# SAM4N_Xplained_Pro_Target_MCU.net
KiCad netlist of a schematic drawn in Altium Designer
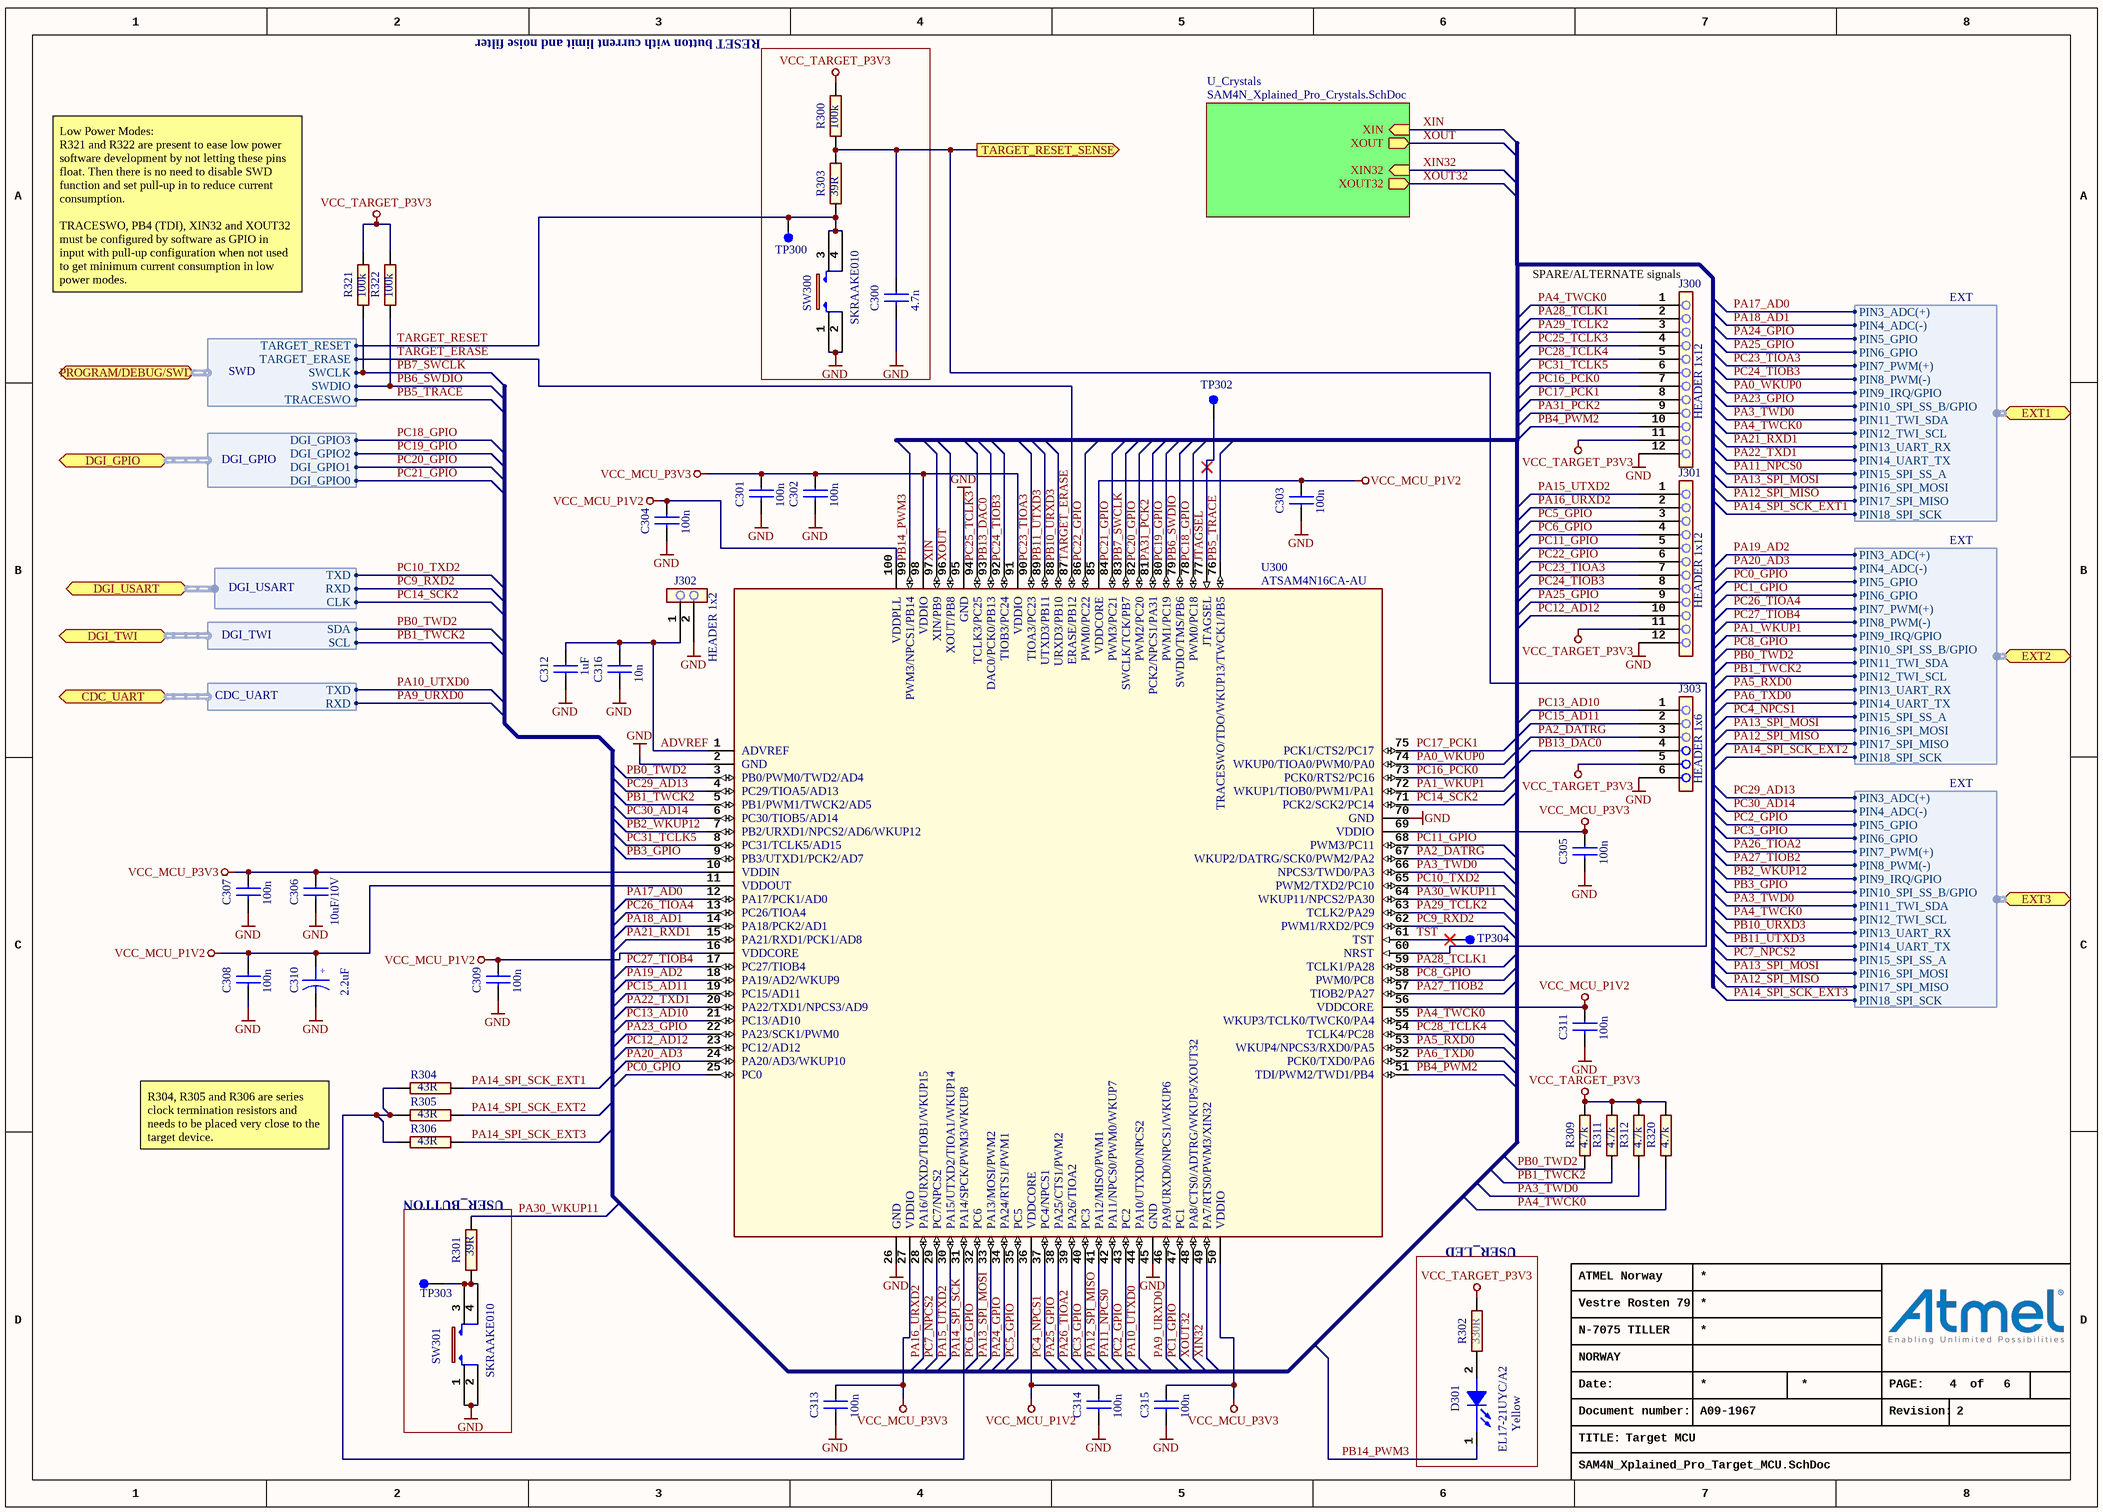
[diagram p0: SAM4N_Xplained_Pro_Target_MCU.SchDoc]

(export (version "E")
  (design (tool "Eeschema 10.0.6"))
  (components
    (comp (ref "C300")
      (value "4.7n")
      (footprint "AP1-00001")
      (description "Ceramic capacitor, SMD 0402, X7R, 25V, +/-10% (de35287)")
      (fields (field (name "TOLERANCE") "25V, +/-10%") (field (name "Comment") "CAP-NONPOL"))
      (libsource (lib "AltiumDbLib") (part "CAP-NONPOL"))
    )
    (comp (ref "C301")
      (value "100n")
      (footprint "AP1-00001")
      (description "Ceramic capacitor, SMD 0402, X7R, 16V, +/-10%")
      (fields (field (name "TOLERANCE") "16V, +/-10%") (field (name "MANUFACTURER") "Kemet"))
      (libsource (lib "AltiumDbLib") (part "CAP-NONPOL"))
    )
    (comp (ref "C302")
      (value "100n")
      (footprint "AP1-00001")
      (description "Ceramic capacitor, SMD 0402, X7R, 16V, +/-10%")
      (fields (field (name "TOLERANCE") "16V, +/-10%") (field (name "MANUFACTURER") "Kemet"))
      (libsource (lib "AltiumDbLib") (part "CAP-NONPOL"))
    )
    (comp (ref "C303")
      (value "100n")
      (footprint "AP1-00001")
      (description "Ceramic capacitor, SMD 0402, X7R, 16V, +/-10%")
      (fields (field (name "TOLERANCE") "16V, +/-10%") (field (name "MANUFACTURER") "Kemet"))
      (libsource (lib "AltiumDbLib") (part "CAP-NONPOL"))
    )
    (comp (ref "C304")
      (value "100n")
      (footprint "AP1-00001")
      (description "Ceramic capacitor, SMD 0402, X7R, 16V, +/-10%")
      (fields (field (name "TOLERANCE") "16V, +/-10%") (field (name "MANUFACTURER") "Kemet"))
      (libsource (lib "AltiumDbLib") (part "CAP-NONPOL"))
    )
    (comp (ref "C305")
      (value "100n")
      (footprint "AP1-00001")
      (description "Ceramic capacitor, SMD 0402, X7R, 16V, +/-10%")
      (fields (field (name "TOLERANCE") "16V, +/-10%") (field (name "MANUFACTURER") "Kemet"))
      (libsource (lib "AltiumDbLib") (part "CAP-NONPOL"))
    )
    (comp (ref "C306")
      (value "10uF/10V")
      (footprint "AP1-00039")
      (description "Ceramic capacitor, SMD 0603, X5R, 10V, 10UF ± 20%")
      (fields (field (name "TOLERANCE") "± 20%") (field (name "MANUFACTURER") "AVX"))
      (libsource (lib "AltiumDbLib") (part "CAP-NONPOL"))
    )
    (comp (ref "C307")
      (value "100n")
      (footprint "AP1-00001")
      (description "Ceramic capacitor, SMD 0402, X7R, 16V, +/-10%")
      (fields (field (name "TOLERANCE") "16V, +/-10%") (field (name "MANUFACTURER") "Kemet"))
      (libsource (lib "AltiumDbLib") (part "CAP-NONPOL"))
    )
    (comp (ref "C308")
      (value "100n")
      (footprint "AP1-00001")
      (description "Ceramic capacitor, SMD 0402, X7R, 16V, +/-10%")
      (fields (field (name "TOLERANCE") "16V, +/-10%") (field (name "MANUFACTURER") "Kemet"))
      (libsource (lib "AltiumDbLib") (part "CAP-NONPOL"))
    )
    (comp (ref "C309")
      (value "100n")
      (footprint "AP1-00001")
      (description "Ceramic capacitor, SMD 0402, X7R, 16V, +/-10%")
      (fields (field (name "TOLERANCE") "16V, +/-10%") (field (name "MANUFACTURER") "Kemet"))
      (libsource (lib "AltiumDbLib") (part "CAP-NONPOL"))
    )
    (comp (ref "C310")
      (value "2.2uF")
      (footprint "AP1-00036")
      (description "Capacitor Tantalum 10V 2.2uF 10% ESR = 6 ohm")
      (fields (field (name "TOLERANCE") "±10%") (field (name "MANUFACTURER") "Kemet"))
      (libsource (lib "AltiumDbLib") (part "CAP-POL"))
    )
    (comp (ref "C311")
      (value "100n")
      (footprint "AP1-00001")
      (description "Ceramic capacitor, SMD 0402, X7R, 16V, +/-10%")
      (fields (field (name "TOLERANCE") "16V, +/-10%") (field (name "MANUFACTURER") "Kemet"))
      (libsource (lib "AltiumDbLib") (part "CAP-NONPOL"))
    )
    (comp (ref "C312")
      (value "1uF")
      (footprint "AP1-00038")
      (description "Ceramic capacitor, SMD 0402, X5R, 10V, ±10 %")
      (fields (field (name "MANUFACTURER") "AVX") (field (name "MPN") "0402ZD105KAT2A"))
      (libsource (lib "AltiumDbLib") (part "CAP-NONPOL"))
    )
    (comp (ref "C313")
      (value "100n")
      (footprint "AP1-00001")
      (description "Ceramic capacitor, SMD 0402, X7R, 16V, +/-10%")
      (fields (field (name "TOLERANCE") "16V, +/-10%") (field (name "MANUFACTURER") "Kemet"))
      (libsource (lib "AltiumDbLib") (part "CAP-NONPOL"))
    )
    (comp (ref "C314")
      (value "100n")
      (footprint "AP1-00001")
      (description "Ceramic capacitor, SMD 0402, X7R, 16V, +/-10%")
      (fields (field (name "TOLERANCE") "16V, +/-10%") (field (name "MANUFACTURER") "Kemet"))
      (libsource (lib "AltiumDbLib") (part "CAP-NONPOL"))
    )
    (comp (ref "C315")
      (value "100n")
      (footprint "AP1-00001")
      (description "Ceramic capacitor, SMD 0402, X7R, 16V, +/-10%")
      (fields (field (name "TOLERANCE") "16V, +/-10%") (field (name "MANUFACTURER") "Kemet"))
      (libsource (lib "AltiumDbLib") (part "CAP-NONPOL"))
    )
    (comp (ref "C316")
      (value "10n")
      (footprint "AP1-00001")
      (description "Ceramic capacitor, SMD 0402, X7R, 25V, +/-10%")
      (fields (field (name "TOLERANCE") "25V, +/-10%") (field (name "Comment") "CAP-NONPOL"))
      (libsource (lib "AltiumDbLib") (part "CAP-NONPOL"))
    )
    (comp (ref "D301")
      (value "Yellow")
      (footprint "AP4-00013")
      (description "LED, Yellow, Wave length=591nm, SMD 0805, ±70°")
      (fields
        (field (name "ALTIUM_VALUE") "EL17-21UYC/A2")
        (field (name "MANUFACTURER") "Everlight")
        (field (name "MPN") "17-21UYC/S530-A3/TR8")
      )
      (libsource (lib "AltiumDbLib") (part "LED_12"))
    )
    (comp (ref "J300")
      (value "HEADER 1x12")
      (footprint "AP8-00677")
      (description "1x12 pin header, 2.54mm pitch, Pin-in-Paste THM")
      (fields (field (name "MANUFACTURER") "SAMTEC") (field (name "MPN") "HMTSW-112-23-F-S-237"))
      (libsource (lib "AltiumDbLib") (part "HEADER 1x12"))
    )
    (comp (ref "J301")
      (value "HEADER 1x12")
      (footprint "AP8-00677")
      (description "1x12 pin header, 2.54mm pitch, Pin-in-Paste THM")
      (fields (field (name "MANUFACTURER") "SAMTEC") (field (name "MPN") "HMTSW-112-23-F-S-237"))
      (libsource (lib "AltiumDbLib") (part "HEADER 1x12"))
    )
    (comp (ref "J302")
      (value "HEADER 1x2")
      (footprint "AP8-00733")
      (description "1x2 pin header, 2.54mm pitch, Pin-in-Paste THM")
      (fields (field (name "MANUFACTURER") "SAMTEC") (field (name "MPN") "HMTSW-102-23-F-S-237"))
      (libsource (lib "AltiumDbLib") (part "HEADER 1x2"))
    )
    (comp (ref "J303")
      (value "HEADER 1x6")
      (footprint "AP8-00676")
      (description "1x6 pin header, 2.54mm pitch, Pin-in-Paste THM")
      (fields (field (name "MANUFACTURER") "SAMTEC") (field (name "MPN") "HMTSW-106-23-F-S-237"))
      (libsource (lib "AltiumDbLib") (part "HEADER 1x6"))
    )
    (comp (ref "R300")
      (value "100k")
      (footprint "AP2-00000")
      (description "Thick film resistor, SMD 0402, 1/16W, 1%")
      (fields (field (name "TOLERANCE") "1 %") (field (name "Comment") "R2"))
      (libsource (lib "AltiumDbLib") (part "R2"))
    )
    (comp (ref "R301")
      (value "39R")
      (footprint "AP2-00000")
      (description "Thick film resistor, SMD 0402, 1/16W, 1%")
      (fields (field (name "TOLERANCE") "1 %") (field (name "Comment") "R2"))
      (libsource (lib "") (part "R2_2"))
    )
    (comp (ref "R302")
      (value "330R")
      (footprint "AP2-00000")
      (description "Thick film resistor, SMD 0402, 1/16W, 1%")
      (fields (field (name "TOLERANCE") "1 %") (field (name "Comment") "R2"))
      (libsource (lib "AltiumDbLib") (part "R2"))
    )
    (comp (ref "R303")
      (value "39R")
      (footprint "AP2-00000")
      (description "Thick film resistor, SMD 0402, 1/16W, 1%")
      (fields (field (name "TOLERANCE") "1 %") (field (name "Comment") "R2"))
      (libsource (lib "AltiumDbLib") (part "R2"))
    )
    (comp (ref "R304")
      (value "43R")
      (footprint "AP2-00000")
      (description "Thick film resistor, SMD 0402, 1/16W, 1%")
      (fields (field (name "TOLERANCE") "1 %") (field (name "Comment") "R2"))
      (libsource (lib "") (part "R2_1"))
    )
    (comp (ref "R305")
      (value "43R")
      (footprint "AP2-00000")
      (description "Thick film resistor, SMD 0402, 1/16W, 1%")
      (fields (field (name "TOLERANCE") "1 %") (field (name "Comment") "R2"))
      (libsource (lib "") (part "R2_1"))
    )
    (comp (ref "R306")
      (value "43R")
      (footprint "AP2-00000")
      (description "Thick film resistor, SMD 0402, 1/16W, 1%")
      (fields (field (name "TOLERANCE") "1 %") (field (name "Comment") "R2"))
      (libsource (lib "") (part "R2_1"))
    )
    (comp (ref "R309")
      (value "4.7k")
      (footprint "AP2-00000")
      (description "Thick film resistor, SMD 0402, 1/16W, 1%")
      (fields (field (name "TOLERANCE") "1 %") (field (name "Comment") "R2"))
      (libsource (lib "AltiumDbLib") (part "R2"))
    )
    (comp (ref "R311")
      (value "4.7k")
      (footprint "AP2-00000")
      (description "Thick film resistor, SMD 0402, 1/16W, 1%")
      (fields (field (name "TOLERANCE") "1 %") (field (name "Comment") "R2"))
      (libsource (lib "AltiumDbLib") (part "R2"))
    )
    (comp (ref "R312")
      (value "4.7k")
      (footprint "AP2-00000")
      (description "Thick film resistor, SMD 0402, 1/16W, 1%")
      (fields (field (name "TOLERANCE") "1 %") (field (name "Comment") "R2"))
      (libsource (lib "AltiumDbLib") (part "R2"))
    )
    (comp (ref "R320")
      (value "4.7k")
      (footprint "AP2-00000")
      (description "Thick film resistor, SMD 0402, 1/16W, 1%")
      (fields (field (name "TOLERANCE") "1 %") (field (name "Comment") "R2"))
      (libsource (lib "AltiumDbLib") (part "R2"))
    )
    (comp (ref "R321")
      (value "100k")
      (footprint "AP2-00000")
      (description "Thick film resistor, SMD 0402, 1/16W, 1%")
      (fields (field (name "TOLERANCE") "1 %") (field (name "Comment") "R2"))
      (libsource (lib "AltiumDbLib") (part "R2"))
    )
    (comp (ref "R322")
      (value "100k")
      (footprint "AP2-00000")
      (description "Thick film resistor, SMD 0402, 1/16W, 1%")
      (fields (field (name "TOLERANCE") "1 %") (field (name "Comment") "R2"))
      (libsource (lib "AltiumDbLib") (part "R2"))
    )
    (comp (ref "SW300")
      (value "SKRAAKE010")
      (footprint "AP8-00137")
      (description "6.2x6.2 mm SMD tact switch, same as A08-0091 but less force is needed")
      (fields
        (field (name "MANUFACTURER") "ALPS")
        (field (name "Comment") "Can be ordered in low volumes from Mouser")
      )
      (libsource (lib "AltiumDbLib") (part "PUSHBUTTON1"))
    )
    (comp (ref "SW301")
      (value "SKRAAKE010")
      (footprint "AP8-00137")
      (description "6.2x6.2 mm SMD tact switch, same as A08-0091 but less force is needed")
      (fields
        (field (name "MANUFACTURER") "ALPS")
        (field (name "Comment") "Can be ordered in low volumes from Mouser")
      )
      (libsource (lib "AltiumDbLib") (part "PUSHBUTTON1"))
    )
    (comp (ref "TP300")
      (value "TESTPAD")
      (footprint "AP8-00010")
      (description "Single SMD testpad")
      (libsource (lib "AltiumDbLib") (part "TESTPOINT"))
    )
    (comp (ref "TP302")
      (value "TESTPOINT")
      (footprint "AP8-00010")
      (description "Single SMD testpad")
      (libsource (lib "AltiumDbLib") (part "TESTPOINT"))
    )
    (comp (ref "TP303")
      (value "TESTPAD")
      (footprint "AP8-00010")
      (description "Single SMD testpad")
      (libsource (lib "AltiumDbLib") (part "TESTPOINT"))
    )
    (comp (ref "TP304")
      (value "TESTPOINT")
      (footprint "AP8-00010")
      (description "Single SMD testpad")
      (libsource (lib "AltiumDbLib") (part "TESTPOINT"))
    )
    (comp (ref "U300")
      (value "ATSAM4N16CA-AU")
      (footprint "AP6-00292")
      (description "ARM Cortex-M4 MCU with 1MB flash, 80KB SRAM")
      (fields (field (name "MANUFACTURER") "ATMEL") (field (name "Comment") "SAM4N_100LPQF"))
      (libsource (lib "AltiumDbLib") (part "SAM4N_100LPQF"))
    )
  )
  (nets
    (net (code "7") (name "/ADVREF") (class "Default")
      (node (ref "C312") (pin "1") (pinfunction "1_1") (pintype "passive"))
      (node (ref "C316") (pin "1") (pinfunction "1_1") (pintype "passive"))
      (node (ref "J302") (pin "1") (pinfunction "1_1") (pintype "passive"))
      (node (ref "U300") (pin "1") (pinfunction "ADVREF_1") (pintype "passive"))
    )
    (net (code "8") (name "/JTAGSEL") (class "Default")
      (node (ref "TP302") (pin "1") (pinfunction "1_1") (pintype "passive"))
      (node (ref "U300") (pin "77") (pinfunction "JTAGSEL_77") (pintype "input"))
    )
    (net (code "9") (name "/PA0_WKUP0") (class "Default")
      (node (ref "U300") (pin "74") (pinfunction "PA0_74") (pintype "bidirectional"))
    )
    (net (code "10") (name "/PA1_WKUP1") (class "Default")
      (node (ref "U300") (pin "72") (pinfunction "PA1_72") (pintype "bidirectional"))
    )
    (net (code "11") (name "/PA2_DATRG") (class "Default")
      (node (ref "J303") (pin "3") (pinfunction "3_3") (pintype "passive"))
      (node (ref "U300") (pin "67") (pinfunction "PA2_67") (pintype "bidirectional"))
    )
    (net (code "12") (name "/PA3_TWD0") (class "Default")
      (node (ref "R312") (pin "1") (pinfunction "1_1") (pintype "passive"))
      (node (ref "U300") (pin "66") (pinfunction "PA3_66") (pintype "bidirectional"))
    )
    (net (code "13") (name "/PA4_TWCK0") (class "Default")
      (node (ref "J300") (pin "1") (pinfunction "1_1") (pintype "passive"))
      (node (ref "R320") (pin "1") (pinfunction "1_1") (pintype "passive"))
      (node (ref "U300") (pin "55") (pinfunction "PA4_55") (pintype "bidirectional"))
    )
    (net (code "14") (name "/PA5_RXD0") (class "Default")
      (node (ref "U300") (pin "53") (pinfunction "PA5_53") (pintype "bidirectional"))
    )
    (net (code "15") (name "/PA6_TXD0") (class "Default")
      (node (ref "U300") (pin "52") (pinfunction "PA6_52") (pintype "bidirectional"))
    )
    (net (code "16") (name "/PA9_URXD0") (class "Default")
      (node (ref "U300") (pin "46") (pinfunction "PA9_46") (pintype "bidirectional"))
    )
    (net (code "17") (name "/PA10_UTXD0") (class "Default")
      (node (ref "U300") (pin "44") (pinfunction "PA10_44") (pintype "bidirectional"))
    )
    (net (code "18") (name "/PA11_NPCS0") (class "Default")
      (node (ref "U300") (pin "42") (pinfunction "PA11_42") (pintype "bidirectional"))
    )
    (net (code "19") (name "/PA12_SPI_MISO") (class "Default")
      (node (ref "U300") (pin "41") (pinfunction "PA12_41") (pintype "bidirectional"))
    )
    (net (code "20") (name "/PA13_SPI_MOSI") (class "Default")
      (node (ref "U300") (pin "33") (pinfunction "PA13_33") (pintype "bidirectional"))
    )
    (net (code "21") (name "/PA14_SPI_SCK") (class "Default")
      (node (ref "R304") (pin "2") (pinfunction "2_2") (pintype "passive"))
      (node (ref "R305") (pin "2") (pinfunction "2_2") (pintype "passive"))
      (node (ref "R306") (pin "2") (pinfunction "2_2") (pintype "passive"))
      (node (ref "U300") (pin "31") (pinfunction "PA14_31") (pintype "bidirectional"))
    )
    (net (code "22") (name "/PA14_SPI_SCK_EXT1") (class "Default")
      (node (ref "R304") (pin "1") (pinfunction "1_1") (pintype "passive"))
    )
    (net (code "23") (name "/PA14_SPI_SCK_EXT2") (class "Default")
      (node (ref "R305") (pin "1") (pinfunction "1_1") (pintype "passive"))
    )
    (net (code "24") (name "/PA14_SPI_SCK_EXT3") (class "Default")
      (node (ref "R306") (pin "1") (pinfunction "1_1") (pintype "passive"))
    )
    (net (code "25") (name "/PA15_UTXD2") (class "Default")
      (node (ref "J301") (pin "1") (pinfunction "1_1") (pintype "passive"))
      (node (ref "U300") (pin "30") (pinfunction "PA15_30") (pintype "bidirectional"))
    )
    (net (code "26") (name "/PA16_URXD2") (class "Default")
      (node (ref "J301") (pin "2") (pinfunction "2_2") (pintype "passive"))
      (node (ref "U300") (pin "28") (pinfunction "PA16_28") (pintype "bidirectional"))
    )
    (net (code "27") (name "/PA17_AD0") (class "Default")
      (node (ref "U300") (pin "12") (pinfunction "PA17_12") (pintype "bidirectional"))
    )
    (net (code "28") (name "/PA18_AD1") (class "Default")
      (node (ref "U300") (pin "14") (pinfunction "PA18_14") (pintype "bidirectional"))
    )
    (net (code "29") (name "/PA19_AD2") (class "Default")
      (node (ref "U300") (pin "18") (pinfunction "PA19_18") (pintype "bidirectional"))
    )
    (net (code "30") (name "/PA20_AD3") (class "Default")
      (node (ref "U300") (pin "24") (pinfunction "PA20_24") (pintype "bidirectional"))
    )
    (net (code "31") (name "/PA21_RXD1") (class "Default")
      (node (ref "U300") (pin "15") (pinfunction "PA21_15") (pintype "bidirectional"))
    )
    (net (code "32") (name "/PA22_TXD1") (class "Default")
      (node (ref "U300") (pin "20") (pinfunction "PA22_20") (pintype "bidirectional"))
    )
    (net (code "33") (name "/PA23_GPIO") (class "Default")
      (node (ref "U300") (pin "22") (pinfunction "PA23_22") (pintype "bidirectional"))
    )
    (net (code "34") (name "/PA24_GPIO") (class "Default")
      (node (ref "U300") (pin "34") (pinfunction "PA24_34") (pintype "bidirectional"))
    )
    (net (code "35") (name "/PA25_GPIO") (class "Default")
      (node (ref "J301") (pin "9") (pinfunction "9_9") (pintype "passive"))
      (node (ref "U300") (pin "38") (pinfunction "PA25_38") (pintype "bidirectional"))
    )
    (net (code "36") (name "/PA26_TIOA2") (class "Default")
      (node (ref "U300") (pin "39") (pinfunction "PA26_39") (pintype "bidirectional"))
    )
    (net (code "37") (name "/PA27_TIOB2") (class "Default")
      (node (ref "U300") (pin "57") (pinfunction "PA27_57") (pintype "bidirectional"))
    )
    (net (code "38") (name "/PA28_TCLK1") (class "Default")
      (node (ref "J300") (pin "2") (pinfunction "2_2") (pintype "passive"))
      (node (ref "U300") (pin "59") (pinfunction "PA28_59") (pintype "bidirectional"))
    )
    (net (code "39") (name "/PA29_TCLK2") (class "Default")
      (node (ref "J300") (pin "3") (pinfunction "3_3") (pintype "passive"))
      (node (ref "U300") (pin "63") (pinfunction "PA29_63") (pintype "bidirectional"))
    )
    (net (code "40") (name "/PA30_WKUP11") (class "Default")
      (node (ref "R301") (pin "2") (pinfunction "2_2") (pintype "passive"))
      (node (ref "U300") (pin "64") (pinfunction "PA30_64") (pintype "bidirectional"))
    )
    (net (code "41") (name "/PA31_PCK2") (class "Default")
      (node (ref "J300") (pin "9") (pinfunction "9_9") (pintype "passive"))
      (node (ref "U300") (pin "81") (pinfunction "PA31_81") (pintype "bidirectional"))
    )
    (net (code "42") (name "/PB0_TWD2") (class "Default")
      (node (ref "R309") (pin "1") (pinfunction "1_1") (pintype "passive"))
      (node (ref "U300") (pin "3") (pinfunction "PB0_3") (pintype "bidirectional"))
    )
    (net (code "43") (name "/PB1_TWCK2") (class "Default")
      (node (ref "R311") (pin "1") (pinfunction "1_1") (pintype "passive"))
      (node (ref "U300") (pin "5") (pinfunction "PB1_5") (pintype "bidirectional"))
    )
    (net (code "44") (name "/PB2_WKUP12") (class "Default")
      (node (ref "U300") (pin "7") (pinfunction "PB2_7") (pintype "bidirectional"))
    )
    (net (code "45") (name "/PB3_GPIO") (class "Default")
      (node (ref "U300") (pin "9") (pinfunction "PB3_9") (pintype "bidirectional"))
    )
    (net (code "46") (name "/PB4_PWM2") (class "Default")
      (node (ref "J300") (pin "10") (pinfunction "10_10") (pintype "passive"))
      (node (ref "U300") (pin "51") (pinfunction "PB4_51") (pintype "bidirectional"))
    )
    (net (code "47") (name "/PB5_TRACE") (class "Default")
      (node (ref "U300") (pin "76") (pinfunction "PB5_76") (pintype "bidirectional"))
    )
    (net (code "48") (name "/PB6_SWDIO") (class "Default")
      (node (ref "R322") (pin "1") (pinfunction "1_1") (pintype "passive"))
      (node (ref "U300") (pin "79") (pinfunction "PB6_79") (pintype "bidirectional"))
    )
    (net (code "49") (name "/PB7_SWCLK") (class "Default")
      (node (ref "R321") (pin "1") (pinfunction "1_1") (pintype "passive"))
      (node (ref "U300") (pin "83") (pinfunction "PB7_83") (pintype "bidirectional"))
    )
    (net (code "50") (name "/PB10_URXD3") (class "Default")
      (node (ref "U300") (pin "88") (pinfunction "PB10_88") (pintype "bidirectional"))
    )
    (net (code "51") (name "/PB11_UTXD3") (class "Default")
      (node (ref "U300") (pin "89") (pinfunction "PB11_89") (pintype "bidirectional"))
    )
    (net (code "52") (name "/PB13_DAC0") (class "Default")
      (node (ref "J303") (pin "4") (pinfunction "4_4") (pintype "passive"))
      (node (ref "U300") (pin "93") (pinfunction "PB13_93") (pintype "bidirectional"))
    )
    (net (code "53") (name "/PB14_PWM3") (class "Default")
      (node (ref "D301") (pin "1") (pinfunction "CATHODE_1") (pintype "passive"))
      (node (ref "U300") (pin "99") (pinfunction "PB14_99") (pintype "bidirectional"))
    )
    (net (code "54") (name "/PC0_GPIO") (class "Default")
      (node (ref "U300") (pin "25") (pinfunction "PC0_25") (pintype "bidirectional"))
    )
    (net (code "55") (name "/PC1_GPIO") (class "Default")
      (node (ref "U300") (pin "47") (pinfunction "PC1_47") (pintype "bidirectional"))
    )
    (net (code "56") (name "/PC2_GPIO") (class "Default")
      (node (ref "U300") (pin "43") (pinfunction "PC2_43") (pintype "bidirectional"))
    )
    (net (code "57") (name "/PC3_GPIO") (class "Default")
      (node (ref "U300") (pin "40") (pinfunction "PC3_40") (pintype "bidirectional"))
    )
    (net (code "58") (name "/PC4_NPCS1") (class "Default")
      (node (ref "U300") (pin "37") (pinfunction "PC4_37") (pintype "bidirectional"))
    )
    (net (code "59") (name "/PC5_GPIO") (class "Default")
      (node (ref "J301") (pin "3") (pinfunction "3_3") (pintype "passive"))
      (node (ref "U300") (pin "35") (pinfunction "PC5_35") (pintype "bidirectional"))
    )
    (net (code "60") (name "/PC6_GPIO") (class "Default")
      (node (ref "J301") (pin "4") (pinfunction "4_4") (pintype "passive"))
      (node (ref "U300") (pin "32") (pinfunction "PC6_32") (pintype "bidirectional"))
    )
    (net (code "61") (name "/PC7_NPCS2") (class "Default")
      (node (ref "U300") (pin "29") (pinfunction "PC7_29") (pintype "bidirectional"))
    )
    (net (code "62") (name "/PC8_GPIO") (class "Default")
      (node (ref "U300") (pin "58") (pinfunction "PC8_58") (pintype "bidirectional"))
    )
    (net (code "63") (name "/PC9_RXD2") (class "Default")
      (node (ref "U300") (pin "62") (pinfunction "PC9_62") (pintype "bidirectional"))
    )
    (net (code "64") (name "/PC10_TXD2") (class "Default")
      (node (ref "U300") (pin "65") (pinfunction "PC10_65") (pintype "bidirectional"))
    )
    (net (code "65") (name "/PC11_GPIO") (class "Default")
      (node (ref "J301") (pin "5") (pinfunction "5_5") (pintype "passive"))
      (node (ref "U300") (pin "68") (pinfunction "PC11_68") (pintype "bidirectional"))
    )
    (net (code "66") (name "/PC12_AD12") (class "Default")
      (node (ref "J301") (pin "10") (pinfunction "10_10") (pintype "passive"))
      (node (ref "U300") (pin "23") (pinfunction "PC12_23") (pintype "bidirectional"))
    )
    (net (code "67") (name "/PC13_AD10") (class "Default")
      (node (ref "J303") (pin "1") (pinfunction "1_1") (pintype "passive"))
      (node (ref "U300") (pin "21") (pinfunction "PC13_21") (pintype "bidirectional"))
    )
    (net (code "68") (name "/PC14_SCK2") (class "Default")
      (node (ref "U300") (pin "71") (pinfunction "PC14_71") (pintype "bidirectional"))
    )
    (net (code "69") (name "/PC15_AD11") (class "Default")
      (node (ref "J303") (pin "2") (pinfunction "2_2") (pintype "passive"))
      (node (ref "U300") (pin "19") (pinfunction "PC15_19") (pintype "bidirectional"))
    )
    (net (code "70") (name "/PC16_PCK0") (class "Default")
      (node (ref "J300") (pin "7") (pinfunction "7_7") (pintype "passive"))
      (node (ref "U300") (pin "73") (pinfunction "PC16_73") (pintype "bidirectional"))
    )
    (net (code "71") (name "/PC17_PCK1") (class "Default")
      (node (ref "J300") (pin "8") (pinfunction "8_8") (pintype "passive"))
      (node (ref "U300") (pin "75") (pinfunction "PC17_75") (pintype "bidirectional"))
    )
    (net (code "72") (name "/PC18_GPIO") (class "Default")
      (node (ref "U300") (pin "78") (pinfunction "PC18_78") (pintype "bidirectional"))
    )
    (net (code "73") (name "/PC19_GPIO") (class "Default")
      (node (ref "U300") (pin "80") (pinfunction "PC19_80") (pintype "bidirectional"))
    )
    (net (code "74") (name "/PC20_GPIO") (class "Default")
      (node (ref "U300") (pin "82") (pinfunction "PC20_82") (pintype "bidirectional"))
    )
    (net (code "75") (name "/PC21_GPIO") (class "Default")
      (node (ref "U300") (pin "84") (pinfunction "PC21_84") (pintype "bidirectional"))
    )
    (net (code "76") (name "/PC22_GPIO") (class "Default")
      (node (ref "J301") (pin "6") (pinfunction "6_6") (pintype "passive"))
      (node (ref "U300") (pin "86") (pinfunction "PC22_86") (pintype "bidirectional"))
    )
    (net (code "77") (name "/PC23_TIOA3") (class "Default")
      (node (ref "J301") (pin "7") (pinfunction "7_7") (pintype "passive"))
      (node (ref "U300") (pin "90") (pinfunction "PC23_90") (pintype "bidirectional"))
    )
    (net (code "78") (name "/PC24_TIOB3") (class "Default")
      (node (ref "J301") (pin "8") (pinfunction "8_8") (pintype "passive"))
      (node (ref "U300") (pin "92") (pinfunction "PC24_92") (pintype "bidirectional"))
    )
    (net (code "79") (name "/PC25_TCLK3") (class "Default")
      (node (ref "J300") (pin "4") (pinfunction "4_4") (pintype "passive"))
      (node (ref "U300") (pin "94") (pinfunction "PC25_94") (pintype "bidirectional"))
    )
    (net (code "80") (name "/PC26_TIOA4") (class "Default")
      (node (ref "U300") (pin "13") (pinfunction "PC26_13") (pintype "bidirectional"))
    )
    (net (code "81") (name "/PC27_TIOB4") (class "Default")
      (node (ref "U300") (pin "17") (pinfunction "PC27_17") (pintype "bidirectional"))
    )
    (net (code "82") (name "/PC28_TCLK4") (class "Default")
      (node (ref "J300") (pin "5") (pinfunction "5_5") (pintype "passive"))
      (node (ref "U300") (pin "54") (pinfunction "PC28_54") (pintype "bidirectional"))
    )
    (net (code "83") (name "/PC29_AD13") (class "Default")
      (node (ref "U300") (pin "4") (pinfunction "PC29_4") (pintype "bidirectional"))
    )
    (net (code "84") (name "/PC30_AD14") (class "Default")
      (node (ref "U300") (pin "6") (pinfunction "PC30_6") (pintype "bidirectional"))
    )
    (net (code "85") (name "/PC31_TCLK5") (class "Default")
      (node (ref "J300") (pin "6") (pinfunction "6_6") (pintype "passive"))
      (node (ref "U300") (pin "8") (pinfunction "PC31_8") (pintype "bidirectional"))
    )
    (net (code "86") (name "/TARGET_ERASE") (class "Default")
      (node (ref "U300") (pin "87") (pinfunction "PB12_87") (pintype "bidirectional"))
    )
    (net (code "87") (name "/TARGET_RESET") (class "Default")
      (node (ref "R303") (pin "1") (pinfunction "1_1") (pintype "passive"))
      (node (ref "SW300") (pin "3") (pinfunction "3_3") (pintype "passive"))
      (node (ref "SW300") (pin "4") (pinfunction "4_4") (pintype "passive"))
      (node (ref "TP300") (pin "1") (pinfunction "1_1") (pintype "passive"))
    )
    (net (code "88") (name "/TARGET_RESET_SENSE") (class "Default")
      (node (ref "C300") (pin "1") (pinfunction "1_1") (pintype "passive"))
      (node (ref "R300") (pin "1") (pinfunction "1_1") (pintype "passive"))
      (node (ref "R303") (pin "2") (pinfunction "2_2") (pintype "passive"))
      (node (ref "U300") (pin "60") (pinfunction "NRST_60") (pintype "input"))
    )
    (net (code "89") (name "/TST") (class "Default")
      (node (ref "TP304") (pin "1") (pinfunction "1_1") (pintype "passive"))
      (node (ref "U300") (pin "61") (pinfunction "TST_61") (pintype "input"))
    )
    (net (code "90") (name "/XIN") (class "Default")
      (node (ref "U300") (pin "97") (pinfunction "PB9_97") (pintype "bidirectional"))
    )
    (net (code "91") (name "/XIN32") (class "Default")
      (node (ref "U300") (pin "49") (pinfunction "PA7_49") (pintype "bidirectional"))
    )
    (net (code "92") (name "/XOUT") (class "Default")
      (node (ref "U300") (pin "96") (pinfunction "PB8_96") (pintype "bidirectional"))
    )
    (net (code "93") (name "/XOUT32") (class "Default")
      (node (ref "U300") (pin "48") (pinfunction "PA8_48") (pintype "bidirectional"))
    )
    (net (code "100") (name "GND") (class "Default")
      (node (ref "C300") (pin "2") (pinfunction "2_2") (pintype "passive"))
      (node (ref "C301") (pin "2") (pinfunction "2_2") (pintype "passive"))
      (node (ref "C302") (pin "2") (pinfunction "2_2") (pintype "passive"))
      (node (ref "C303") (pin "2") (pinfunction "2_2") (pintype "passive"))
      (node (ref "C304") (pin "2") (pinfunction "2_2") (pintype "passive"))
      (node (ref "C305") (pin "2") (pinfunction "2_2") (pintype "passive"))
      (node (ref "C306") (pin "2") (pinfunction "2_2") (pintype "passive"))
      (node (ref "C307") (pin "2") (pinfunction "2_2") (pintype "passive"))
      (node (ref "C308") (pin "2") (pinfunction "2_2") (pintype "passive"))
      (node (ref "C309") (pin "2") (pinfunction "2_2") (pintype "passive"))
      (node (ref "C310") (pin "2") (pinfunction "2_2") (pintype "passive"))
      (node (ref "C311") (pin "2") (pinfunction "2_2") (pintype "passive"))
      (node (ref "C312") (pin "2") (pinfunction "2_2") (pintype "passive"))
      (node (ref "C313") (pin "2") (pinfunction "2_2") (pintype "passive"))
      (node (ref "C314") (pin "2") (pinfunction "2_2") (pintype "passive"))
      (node (ref "C315") (pin "2") (pinfunction "2_2") (pintype "passive"))
      (node (ref "C316") (pin "2") (pinfunction "2_2") (pintype "passive"))
      (node (ref "J300") (pin "12") (pinfunction "12_12") (pintype "passive"))
      (node (ref "J301") (pin "12") (pinfunction "12_12") (pintype "passive"))
      (node (ref "J302") (pin "2") (pinfunction "2_2") (pintype "passive"))
      (node (ref "J303") (pin "6") (pinfunction "6_6") (pintype "passive"))
      (node (ref "SW300") (pin "1") (pinfunction "1_1") (pintype "passive"))
      (node (ref "SW300") (pin "2") (pinfunction "2_2") (pintype "passive"))
      (node (ref "SW301") (pin "1") (pinfunction "1_1") (pintype "passive"))
      (node (ref "SW301") (pin "2") (pinfunction "2_2") (pintype "passive"))
      (node (ref "U300") (pin "2") (pinfunction "GND_2_2") (pintype "power_in"))
      (node (ref "U300") (pin "26") (pinfunction "GND_26_26") (pintype "power_in"))
      (node (ref "U300") (pin "45") (pinfunction "GND_45_45") (pintype "power_in"))
      (node (ref "U300") (pin "70") (pinfunction "GND_70_70") (pintype "power_in"))
      (node (ref "U300") (pin "95") (pinfunction "GND_95_95") (pintype "power_in"))
    )
    (net (code "101") (name "Net-(D301-ANODE)") (class "Default")
      (node (ref "D301") (pin "2") (pinfunction "ANODE_2") (pintype "passive"))
      (node (ref "R302") (pin "1") (pinfunction "1_1") (pintype "passive"))
    )
    (net (code "102") (name "Net-(R301-Pad1)") (class "Default")
      (node (ref "R301") (pin "1") (pinfunction "1_1") (pintype "passive"))
      (node (ref "SW301") (pin "3") (pinfunction "3_3") (pintype "passive"))
      (node (ref "SW301") (pin "4") (pinfunction "4_4") (pintype "passive"))
      (node (ref "TP303") (pin "1") (pinfunction "1_1") (pintype "passive"))
    )
    (net (code "103") (name "VCC_MCU_P1V2") (class "Default")
      (node (ref "C303") (pin "1") (pinfunction "1_1") (pintype "passive"))
      (node (ref "C304") (pin "1") (pinfunction "1_1") (pintype "passive"))
      (node (ref "C308") (pin "1") (pinfunction "1_1") (pintype "passive"))
      (node (ref "C309") (pin "1") (pinfunction "1_1") (pintype "passive"))
      (node (ref "C310") (pin "1") (pinfunction "1_1") (pintype "passive"))
      (node (ref "C311") (pin "1") (pinfunction "1_1") (pintype "passive"))
      (node (ref "C314") (pin "1") (pinfunction "1_1") (pintype "passive"))
      (node (ref "U300") (pin "100") (pinfunction "VDDPLL_100") (pintype "power_in"))
      (node (ref "U300") (pin "11") (pinfunction "VDDOUT_11") (pintype "power_in"))
      (node (ref "U300") (pin "16") (pinfunction "VDDCORE_16_16") (pintype "power_in"))
      (node (ref "U300") (pin "36") (pinfunction "VDDCORE_36_36") (pintype "power_in"))
      (node (ref "U300") (pin "56") (pinfunction "VDDCORE_56_56") (pintype "power_in"))
      (node (ref "U300") (pin "85") (pinfunction "VDDCORE_85_85") (pintype "power_in"))
    )
    (net (code "104") (name "VCC_MCU_P3V3") (class "Default")
      (node (ref "C301") (pin "1") (pinfunction "1_1") (pintype "passive"))
      (node (ref "C302") (pin "1") (pinfunction "1_1") (pintype "passive"))
      (node (ref "C305") (pin "1") (pinfunction "1_1") (pintype "passive"))
      (node (ref "C306") (pin "1") (pinfunction "1_1") (pintype "passive"))
      (node (ref "C307") (pin "1") (pinfunction "1_1") (pintype "passive"))
      (node (ref "C313") (pin "1") (pinfunction "1_1") (pintype "passive"))
      (node (ref "C315") (pin "1") (pinfunction "1_1") (pintype "passive"))
      (node (ref "U300") (pin "10") (pinfunction "VDDIN_10") (pintype "power_in"))
      (node (ref "U300") (pin "27") (pinfunction "VDDIO_27_27") (pintype "power_in"))
      (node (ref "U300") (pin "50") (pinfunction "VDDIO_50_50") (pintype "power_in"))
      (node (ref "U300") (pin "69") (pinfunction "VDDIO_69_69") (pintype "power_in"))
      (node (ref "U300") (pin "91") (pinfunction "VDDIO_91_91") (pintype "power_in"))
      (node (ref "U300") (pin "98") (pinfunction "VDDIO_98_98") (pintype "power_in"))
    )
    (net (code "105") (name "VCC_TARGET_P3V3") (class "Default")
      (node (ref "J300") (pin "11") (pinfunction "11_11") (pintype "passive"))
      (node (ref "J301") (pin "11") (pinfunction "11_11") (pintype "passive"))
      (node (ref "J303") (pin "5") (pinfunction "5_5") (pintype "passive"))
      (node (ref "R300") (pin "2") (pinfunction "2_2") (pintype "passive"))
      (node (ref "R302") (pin "2") (pinfunction "2_2") (pintype "passive"))
      (node (ref "R309") (pin "2") (pinfunction "2_2") (pintype "passive"))
      (node (ref "R311") (pin "2") (pinfunction "2_2") (pintype "passive"))
      (node (ref "R312") (pin "2") (pinfunction "2_2") (pintype "passive"))
      (node (ref "R320") (pin "2") (pinfunction "2_2") (pintype "passive"))
      (node (ref "R321") (pin "2") (pinfunction "2_2") (pintype "passive"))
      (node (ref "R322") (pin "2") (pinfunction "2_2") (pintype "passive"))
    )
  )
)
